# midi_inoutthru.net
KiCad netlist of a schematic drawn in EAGLE
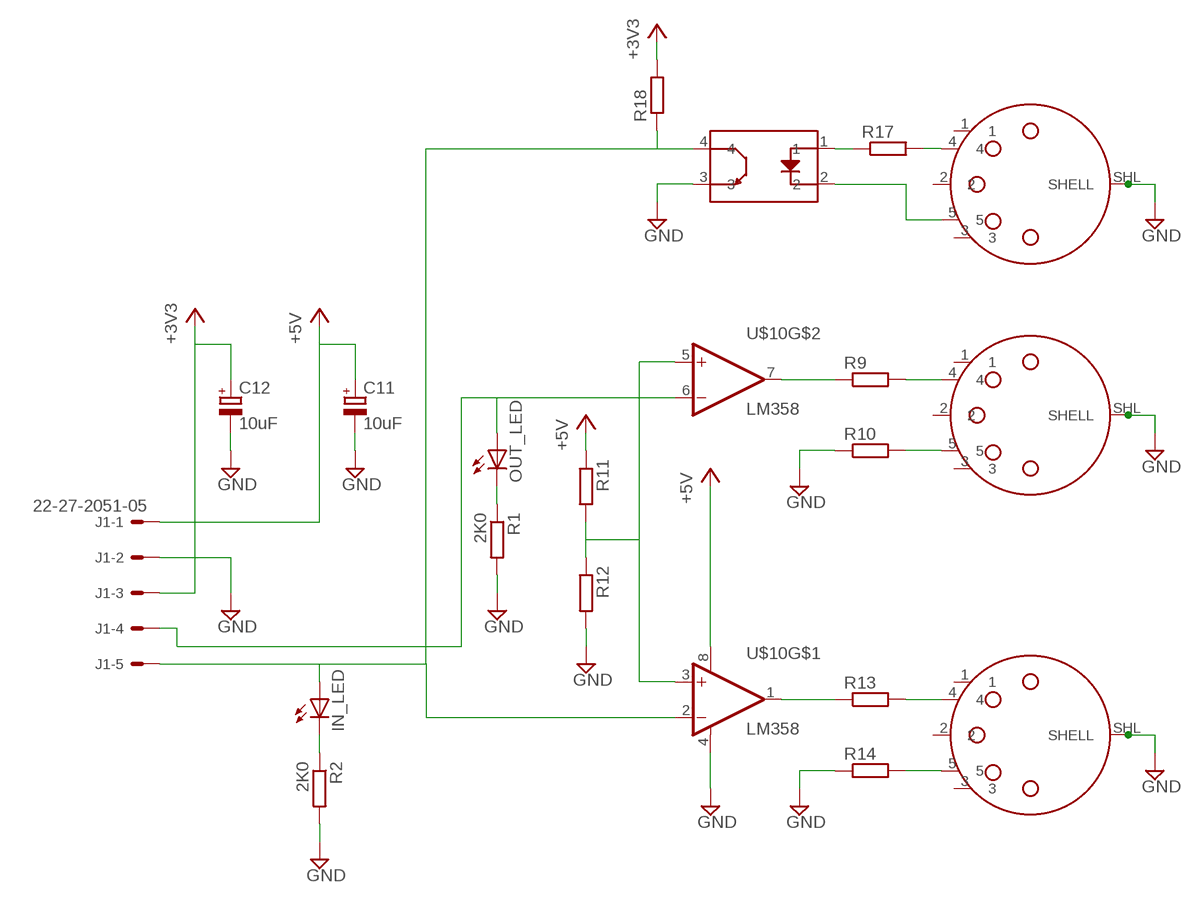
[diagram p0: schematic, sheet 1]

(export (version "E")
  (design (tool "Eeschema 10.0.6"))
  (components
    (comp (ref "C11")
      (value "10uF")
      (footprint "eagle-import:SMC_C")
      (libsource (lib "eagle-import") (part "CPOL-EUSMCC"))
    )
    (comp (ref "C12")
      (value "10uF")
      (footprint "eagle-import:SMC_C")
      (libsource (lib "eagle-import") (part "CPOL-EUSMCC"))
    )
    (comp (ref "IN_LED")
      (value "LEDCHIP-LED0805")
      (footprint "eagle-import:CHIP-LED0805")
      (libsource (lib "eagle-import") (part "LEDCHIP-LED0805"))
    )
    (comp (ref "J1")
      (value "22-27-2051-05")
      (footprint "eagle-import:6410-05")
      (libsource (lib "eagle-import") (part "22-?-0527-2051"))
    )
    (comp (ref "OUT_LED")
      (value "LEDCHIP-LED0805")
      (footprint "eagle-import:CHIP-LED0805")
      (libsource (lib "eagle-import") (part "LEDCHIP-LED0805"))
    )
    (comp (ref "R1")
      (value "2K0")
      (footprint "eagle-import:R0402")
      (libsource (lib "eagle-import") (part "R-EU_R0402"))
    )
    (comp (ref "R2")
      (value "2K0")
      (footprint "eagle-import:R0402")
      (libsource (lib "eagle-import") (part "R-EU_R0402"))
    )
    (comp (ref "R9")
      (value "R-EU_R1206")
      (footprint "eagle-import:R1206")
      (libsource (lib "eagle-import") (part "R-EU_R1206"))
    )
    (comp (ref "R10")
      (value "R-EU_R1206")
      (footprint "eagle-import:R1206")
      (libsource (lib "eagle-import") (part "R-EU_R1206"))
    )
    (comp (ref "R11")
      (value "R-EU_R0402")
      (footprint "eagle-import:R0402")
      (libsource (lib "eagle-import") (part "R-EU_R0402"))
    )
    (comp (ref "R12")
      (value "R-EU_R0402")
      (footprint "eagle-import:R0402")
      (libsource (lib "eagle-import") (part "R-EU_R0402"))
    )
    (comp (ref "R13")
      (value "R-EU_R1206")
      (footprint "eagle-import:R1206")
      (libsource (lib "eagle-import") (part "R-EU_R1206"))
    )
    (comp (ref "R14")
      (value "R-EU_R1206")
      (footprint "eagle-import:R1206")
      (libsource (lib "eagle-import") (part "R-EU_R1206"))
    )
    (comp (ref "R17")
      (value "R-EU_R1206")
      (footprint "eagle-import:R1206")
      (libsource (lib "eagle-import") (part "R-EU_R1206"))
    )
    (comp (ref "R18")
      (value "R-EU_R1206")
      (footprint "eagle-import:R1206")
      (libsource (lib "eagle-import") (part "R-EU_R1206"))
    )
    (comp (ref "U$9")
      (value "MIDI_VERT")
      (footprint "eagle-import:DIN-5_VERT")
      (libsource (lib "eagle-import") (part "MIDI_VERT"))
    )
    (comp (ref "U$10")
      (value "LM358")
      (footprint "eagle-import:SO08")
      (libsource (lib "eagle-import") (part "LM358"))
    )
    (comp (ref "U$11")
      (value "MIDI_VERT")
      (footprint "eagle-import:DIN-5_VERT")
      (libsource (lib "eagle-import") (part "MIDI_VERT"))
    )
    (comp (ref "U$19")
      (value "F2801A")
      (footprint "eagle-import:LONG_TSOP")
      (libsource (lib "eagle-import") (part "F2801A"))
    )
    (comp (ref "U$20")
      (value "MIDI_VERT")
      (footprint "eagle-import:DIN-5_VERT")
      (libsource (lib "eagle-import") (part "MIDI_VERT"))
    )
  )
  (nets
    (net (code "1") (name "+3V3") (class "Default")
      (node (ref "C12") (pin "+") (pinfunction "+_+") (pintype "passive"))
      (node (ref "J1") (pin "3") (pinfunction "S_3") (pintype "passive"))
      (node (ref "R18") (pin "2") (pinfunction "2_2") (pintype "passive"))
    )
    (net (code "2") (name "+5V") (class "Default")
      (node (ref "C11") (pin "+") (pinfunction "+_+") (pintype "passive"))
      (node (ref "J1") (pin "1") (pinfunction "S_1") (pintype "passive"))
      (node (ref "R11") (pin "1") (pinfunction "1_1") (pintype "passive"))
      (node (ref "U$10") (pin "8") (pinfunction "V+_8") (pintype "power_in"))
    )
    (net (code "3") (name "GND") (class "Default")
      (node (ref "C11") (pin "-") (pinfunction "-_-") (pintype "passive"))
      (node (ref "C12") (pin "-") (pinfunction "-_-") (pintype "passive"))
      (node (ref "J1") (pin "2") (pinfunction "S_2") (pintype "passive"))
      (node (ref "R1") (pin "2") (pinfunction "2_2") (pintype "passive"))
      (node (ref "R10") (pin "1") (pinfunction "1_1") (pintype "passive"))
      (node (ref "R12") (pin "2") (pinfunction "2_2") (pintype "passive"))
      (node (ref "R14") (pin "1") (pinfunction "1_1") (pintype "passive"))
      (node (ref "R2") (pin "2") (pinfunction "2_2") (pintype "passive"))
      (node (ref "U$10") (pin "4") (pinfunction "V-_4") (pintype "power_in"))
      (node (ref "U$11") (pin "SHL") (pinfunction "SHELL_SHL") (pintype "input"))
      (node (ref "U$19") (pin "3") (pinfunction "3_3") (pintype "bidirectional"))
      (node (ref "U$20") (pin "SHL") (pinfunction "SHELL_SHL") (pintype "input"))
      (node (ref "U$9") (pin "SHL") (pinfunction "SHELL_SHL") (pintype "input"))
    )
    (net (code "4") (name "Net-(IN_LED-PadC)") (class "Default")
      (node (ref "IN_LED") (pin "C") (pinfunction "C_C") (pintype "passive"))
      (node (ref "R2") (pin "1") (pinfunction "1_1") (pintype "passive"))
    )
    (net (code "5") (name "Net-(J1D-S)") (class "Default")
      (node (ref "J1") (pin "4") (pinfunction "S_4") (pintype "passive"))
      (node (ref "OUT_LED") (pin "A") (pinfunction "A_A") (pintype "passive"))
      (node (ref "U$10") (pin "6") (pinfunction "-IN_6") (pintype "input"))
    )
    (net (code "6") (name "Net-(J1E-S)") (class "Default")
      (node (ref "IN_LED") (pin "A") (pinfunction "A_A") (pintype "passive"))
      (node (ref "J1") (pin "5") (pinfunction "S_5") (pintype "passive"))
      (node (ref "R18") (pin "1") (pinfunction "1_1") (pintype "passive"))
      (node (ref "U$10") (pin "2") (pinfunction "-IN_2") (pintype "input"))
      (node (ref "U$19") (pin "4") (pinfunction "4_4") (pintype "bidirectional"))
    )
    (net (code "7") (name "Net-(OUT_LED-PadC)") (class "Default")
      (node (ref "OUT_LED") (pin "C") (pinfunction "C_C") (pintype "passive"))
      (node (ref "R1") (pin "1") (pinfunction "1_1") (pintype "passive"))
    )
    (net (code "8") (name "Net-(R9-Pad2)") (class "Default")
      (node (ref "R9") (pin "2") (pinfunction "2_2") (pintype "passive"))
      (node (ref "U$9") (pin "4") (pinfunction "4_4") (pintype "input"))
    )
    (net (code "9") (name "Net-(R10-Pad2)") (class "Default")
      (node (ref "R10") (pin "2") (pinfunction "2_2") (pintype "passive"))
      (node (ref "U$9") (pin "5") (pinfunction "5_5") (pintype "input"))
    )
    (net (code "10") (name "Net-(R13-Pad2)") (class "Default")
      (node (ref "R13") (pin "2") (pinfunction "2_2") (pintype "passive"))
      (node (ref "U$11") (pin "4") (pinfunction "4_4") (pintype "input"))
    )
    (net (code "11") (name "Net-(R14-Pad2)") (class "Default")
      (node (ref "R14") (pin "2") (pinfunction "2_2") (pintype "passive"))
      (node (ref "U$11") (pin "5") (pinfunction "5_5") (pintype "input"))
    )
    (net (code "12") (name "Net-(R17-Pad1)") (class "Default")
      (node (ref "R17") (pin "1") (pinfunction "1_1") (pintype "passive"))
      (node (ref "U$19") (pin "1") (pinfunction "1_1") (pintype "bidirectional"))
    )
    (net (code "13") (name "Net-(R17-Pad2)") (class "Default")
      (node (ref "R17") (pin "2") (pinfunction "2_2") (pintype "passive"))
      (node (ref "U$20") (pin "4") (pinfunction "4_4") (pintype "input"))
    )
    (net (code "14") (name "Net-(U$10A-+IN)") (class "Default")
      (node (ref "R11") (pin "2") (pinfunction "2_2") (pintype "passive"))
      (node (ref "R12") (pin "1") (pinfunction "1_1") (pintype "passive"))
      (node (ref "U$10") (pin "3") (pinfunction "+IN_3") (pintype "input"))
      (node (ref "U$10") (pin "5") (pinfunction "+IN_5") (pintype "input"))
    )
    (net (code "15") (name "Net-(U$10A-OUT)") (class "Default")
      (node (ref "R13") (pin "1") (pinfunction "1_1") (pintype "passive"))
      (node (ref "U$10") (pin "1") (pinfunction "OUT_1") (pintype "output"))
    )
    (net (code "16") (name "Net-(U$10B-OUT)") (class "Default")
      (node (ref "R9") (pin "1") (pinfunction "1_1") (pintype "passive"))
      (node (ref "U$10") (pin "7") (pinfunction "OUT_7") (pintype "output"))
    )
    (net (code "17") (name "Net-(U$19-Pad2)") (class "Default")
      (node (ref "U$19") (pin "2") (pinfunction "2_2") (pintype "bidirectional"))
      (node (ref "U$20") (pin "5") (pinfunction "5_5") (pintype "input"))
    )
    (net (code "18") (name "unconnected-(U$9-Pad1)") (class "Default")
      (node (ref "U$9") (pin "1") (pinfunction "1_1") (pintype "input"))
    )
    (net (code "19") (name "unconnected-(U$9-Pad2)") (class "Default")
      (node (ref "U$9") (pin "2") (pinfunction "2_2") (pintype "input"))
    )
    (net (code "20") (name "unconnected-(U$9-Pad3)") (class "Default")
      (node (ref "U$9") (pin "3") (pinfunction "3_3") (pintype "input"))
    )
    (net (code "21") (name "unconnected-(U$11-Pad1)") (class "Default")
      (node (ref "U$11") (pin "1") (pinfunction "1_1") (pintype "input"))
    )
    (net (code "22") (name "unconnected-(U$11-Pad2)") (class "Default")
      (node (ref "U$11") (pin "2") (pinfunction "2_2") (pintype "input"))
    )
    (net (code "23") (name "unconnected-(U$11-Pad3)") (class "Default")
      (node (ref "U$11") (pin "3") (pinfunction "3_3") (pintype "input"))
    )
    (net (code "24") (name "unconnected-(U$20-Pad1)") (class "Default")
      (node (ref "U$20") (pin "1") (pinfunction "1_1") (pintype "input"))
    )
    (net (code "25") (name "unconnected-(U$20-Pad2)") (class "Default")
      (node (ref "U$20") (pin "2") (pinfunction "2_2") (pintype "input"))
    )
    (net (code "26") (name "unconnected-(U$20-Pad3)") (class "Default")
      (node (ref "U$20") (pin "3") (pinfunction "3_3") (pintype "input"))
    )
  )
)
